# BSheet3.net
KiCad netlist of a schematic drawn in Altium Designer
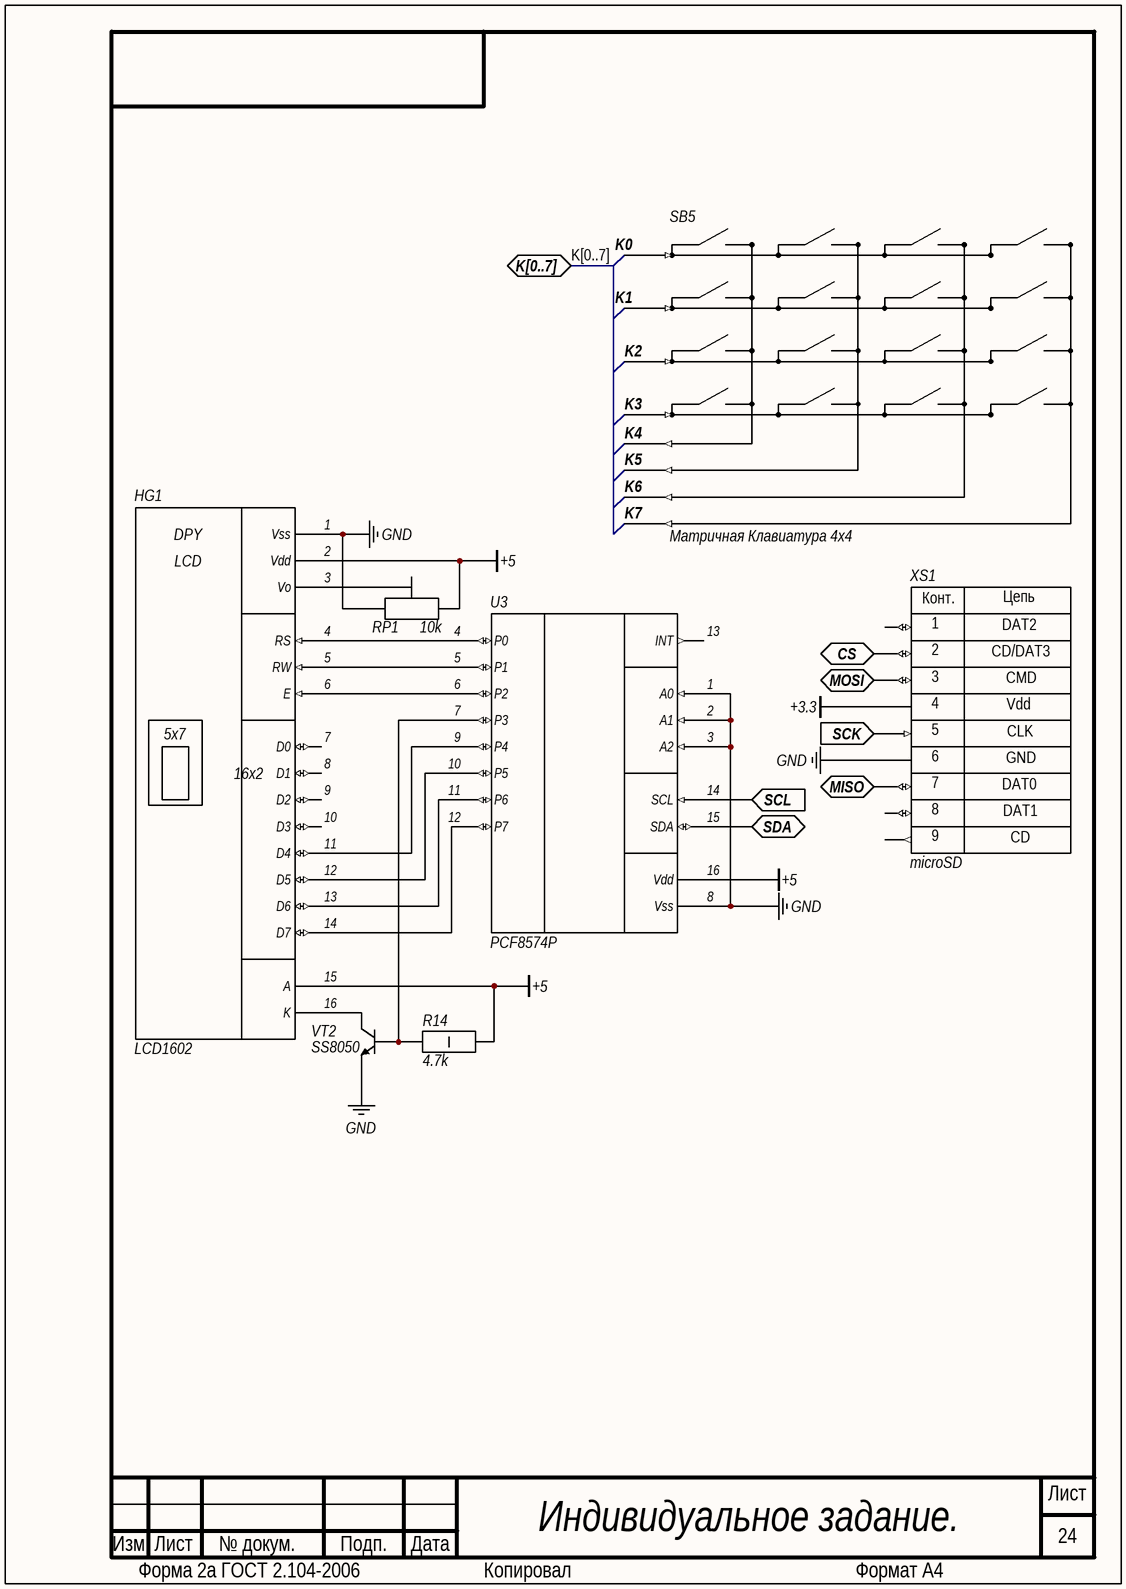
[diagram p0: BSheet3.SchDoc]

(export (version "E")
  (design (tool "Eeschema 10.0.6"))
  (components
    (comp (ref "HG1")
      (value "LCD1602")
      (footprint "X PBS-16")
      (description "Дисплей на основе контроллера HD44780.")
      (libsource (lib "Schlib") (part "LCD HD44780"))
    )
    (comp (ref "R14")
      (value "4.7k")
      (footprint "R AXIAL-1W")
      (fields (field (name "POWER") "1"))
      (libsource (lib "Schlib") (part "Резистор 1 Вт"))
    )
    (comp (ref "RP1")
      (value "10k")
      (footprint "R ADJ-3296W")
      (libsource (lib "Schlib") (part "Подстроечный Резистор"))
    )
    (comp (ref "SB5")
      (value "Матричная Клавиатура 4x4")
      (footprint "X PLS-8")
      (libsource (lib "Schlib") (part "Матричная Клавиатура 4x4"))
    )
    (comp (ref "U3")
      (value "PCF8574P")
      (footprint "U DIP-16")
      (description "IIC расширитель.")
      (libsource (lib "Schlib") (part "PCF8574"))
    )
    (comp (ref "VT2")
      (value "SS8050")
      (footprint "VT TO-92")
      (libsource (lib "Schlib") (part "Биполярный Транзистор"))
    )
    (comp (ref "XS1")
      (value "microSD")
      (footprint "X microSD")
      (description "Слот для карты памяти.")
      (fields (field (name "MANUFACTURER") "Molex"))
      (libsource (lib "Schlib") (part "microSD"))
    )
  )
  (nets
    (net (code "1") (name "+3.3") (class "Default")
      (node (ref "XS1") (pin "4") (pinfunction "Vdd_4") (pintype "power_in"))
    )
    (net (code "2") (name "+5") (class "Default")
      (node (ref "HG1") (pin "15") (pinfunction "A_15") (pintype "power_in"))
      (node (ref "HG1") (pin "2") (pinfunction "Vdd_2") (pintype "power_in"))
      (node (ref "R14") (pin "1") (pintype "power_in"))
      (node (ref "RP1") (pin "1") (pintype "power_in"))
      (node (ref "U3") (pin "16") (pinfunction "Vdd_16") (pintype "power_in"))
    )
    (net (code "3") (name "/CS") (class "Default")
      (node (ref "XS1") (pin "2") (pinfunction "CD/DAT3_2") (pintype "bidirectional"))
    )
    (net (code "4") (name "/K0") (class "Default") (node (ref "SB5") (pin "1") (pintype "input")))
    (net (code "5") (name "/K1") (class "Default") (node (ref "SB5") (pin "2") (pintype "input")))
    (net (code "6") (name "/K2") (class "Default") (node (ref "SB5") (pin "3") (pintype "input")))
    (net (code "7") (name "/K3") (class "Default") (node (ref "SB5") (pin "4") (pintype "input")))
    (net (code "8") (name "/K4") (class "Default") (node (ref "SB5") (pin "5") (pintype "output")))
    (net (code "9") (name "/K5") (class "Default") (node (ref "SB5") (pin "6") (pintype "output")))
    (net (code "10") (name "/K6") (class "Default") (node (ref "SB5") (pin "7") (pintype "output")))
    (net (code "11") (name "/K7") (class "Default") (node (ref "SB5") (pin "8") (pintype "output")))
    (net (code "13") (name "/MISO") (class "Default")
      (node (ref "XS1") (pin "7") (pinfunction "DATA0_7") (pintype "bidirectional"))
    )
    (net (code "14") (name "/MOSI") (class "Default")
      (node (ref "XS1") (pin "3") (pinfunction "CMD_3") (pintype "bidirectional"))
    )
    (net (code "15") (name "/SCK") (class "Default")
      (node (ref "XS1") (pin "5") (pinfunction "CLK_5") (pintype "input"))
    )
    (net (code "16") (name "/SCL") (class "Default")
      (node (ref "U3") (pin "14") (pinfunction "SCL_14") (pintype "input"))
    )
    (net (code "17") (name "/SDA") (class "Default")
      (node (ref "U3") (pin "15") (pinfunction "SDA_15") (pintype "bidirectional"))
    )
    (net (code "18") (name "GND") (class "Default")
      (node (ref "HG1") (pin "1") (pinfunction "Vss_1") (pintype "power_in"))
      (node (ref "RP1") (pin "3") (pintype "power_in"))
      (node (ref "U3") (pin "1") (pinfunction "A0_1") (pintype "input"))
      (node (ref "U3") (pin "2") (pinfunction "A1_2") (pintype "input"))
      (node (ref "U3") (pin "3") (pinfunction "A2_3") (pintype "input"))
      (node (ref "U3") (pin "8") (pinfunction "Vss_8") (pintype "power_in"))
      (node (ref "VT2") (pin "1") (pinfunction "E_1") (pintype "open_emitter"))
      (node (ref "XS1") (pin "6") (pinfunction "GND_6") (pintype "power_in"))
    )
    (net (code "19") (name "Net-(HG1-D4)") (class "Default")
      (node (ref "HG1") (pin "11") (pinfunction "D4_11") (pintype "bidirectional"))
      (node (ref "U3") (pin "9") (pinfunction "P4_9") (pintype "bidirectional"))
    )
    (net (code "20") (name "Net-(HG1-D5)") (class "Default")
      (node (ref "HG1") (pin "12") (pinfunction "D5_12") (pintype "bidirectional"))
      (node (ref "U3") (pin "10") (pinfunction "P5_10") (pintype "bidirectional"))
    )
    (net (code "21") (name "Net-(HG1-D6)") (class "Default")
      (node (ref "HG1") (pin "13") (pinfunction "D6_13") (pintype "bidirectional"))
      (node (ref "U3") (pin "11") (pinfunction "P6_11") (pintype "bidirectional"))
    )
    (net (code "22") (name "Net-(HG1-D7)") (class "Default")
      (node (ref "HG1") (pin "14") (pinfunction "D7_14") (pintype "bidirectional"))
      (node (ref "U3") (pin "12") (pinfunction "P7_12") (pintype "bidirectional"))
    )
    (net (code "23") (name "Net-(HG1-E)") (class "Default")
      (node (ref "HG1") (pin "6") (pinfunction "E_6") (pintype "input"))
      (node (ref "U3") (pin "6") (pinfunction "P2_6") (pintype "bidirectional"))
    )
    (net (code "24") (name "Net-(HG1-K)") (class "Default")
      (node (ref "HG1") (pin "16") (pinfunction "K_16") (pintype "power_in"))
      (node (ref "VT2") (pin "3") (pinfunction "C_3") (pintype "open_collector"))
    )
    (net (code "25") (name "Net-(HG1-RS)") (class "Default")
      (node (ref "HG1") (pin "4") (pinfunction "RS_4") (pintype "input"))
      (node (ref "U3") (pin "4") (pinfunction "P0_4") (pintype "bidirectional"))
    )
    (net (code "26") (name "Net-(HG1-RW)") (class "Default")
      (node (ref "HG1") (pin "5") (pinfunction "RW_5") (pintype "input"))
      (node (ref "U3") (pin "5") (pinfunction "P1_5") (pintype "bidirectional"))
    )
    (net (code "27") (name "Net-(HG1-Vo)") (class "Default")
      (node (ref "HG1") (pin "3") (pinfunction "Vo_3") (pintype "power_in"))
      (node (ref "RP1") (pin "2") (pintype "power_in"))
    )
    (net (code "28") (name "Net-(U3-P3)") (class "Default")
      (node (ref "R14") (pin "2") (pintype "power_in"))
      (node (ref "U3") (pin "7") (pinfunction "P3_7") (pintype "bidirectional"))
      (node (ref "VT2") (pin "2") (pinfunction "B_2") (pintype "passive"))
    )
    (net (code "29") (name "unconnected-(HG1-D0-Pad7)") (class "Default")
      (node (ref "HG1") (pin "7") (pinfunction "D0_7") (pintype "bidirectional"))
    )
    (net (code "30") (name "unconnected-(HG1-D1-Pad8)") (class "Default")
      (node (ref "HG1") (pin "8") (pinfunction "D1_8") (pintype "bidirectional"))
    )
    (net (code "31") (name "unconnected-(HG1-D2-Pad9)") (class "Default")
      (node (ref "HG1") (pin "9") (pinfunction "D2_9") (pintype "bidirectional"))
    )
    (net (code "32") (name "unconnected-(HG1-D3-Pad10)") (class "Default")
      (node (ref "HG1") (pin "10") (pinfunction "D3_10") (pintype "bidirectional"))
    )
    (net (code "33") (name "unconnected-(U3-INT-Pad13)") (class "Default")
      (node (ref "U3") (pin "13") (pinfunction "INT_13") (pintype "output"))
    )
    (net (code "34") (name "unconnected-(XS1-CD-Pad4)") (class "Default")
      (node (ref "XS1") (pin "4") (pinfunction "CD_4") (pintype "output"))
    )
    (net (code "35") (name "unconnected-(XS1-DAT2-Pad1)") (class "Default")
      (node (ref "XS1") (pin "1") (pinfunction "DAT2_1") (pintype "bidirectional"))
    )
    (net (code "36") (name "unconnected-(XS1-DATA1-Pad8)") (class "Default")
      (node (ref "XS1") (pin "8") (pinfunction "DATA1_8") (pintype "bidirectional"))
    )
  )
)
